# 08_-_TEMP_CONTROL.net
KiCad netlist of a schematic drawn in Altium Designer
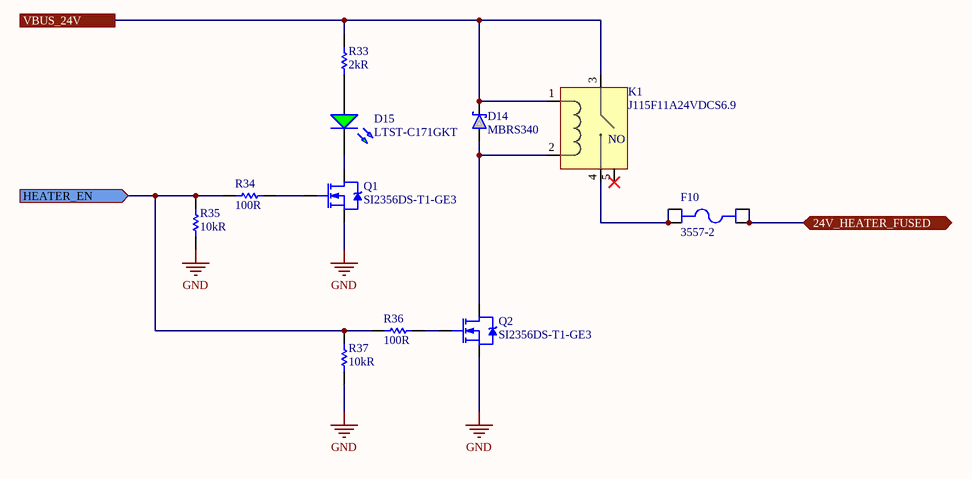
[diagram p0: [08] - TEMP CONTROL.SchDoc]

(export (version "E")
  (design (tool "Eeschema 10.0.6"))
  (components
    (comp (ref "D14")
      (value "MBRS340")
      (footprint "D0-214AB SMC - L")
      (description "DIODE SCHOTTKY 40V 4A SMC")
      (fields (field (name "MANUFACTURER") "ON Semiconductor / Fairchild"))
      (libsource (lib "Diodes") (part "MBRS340"))
    )
    (comp (ref "D15")
      (value "LTST-C171GKT")
      (footprint "LED - 0805 - GREEN")
      (fields (field (name "MANUFACTURER") "Vishay Lite-On"))
      (libsource (lib "LEDs") (part "LTST-C171GKT"))
    )
    (comp (ref "F10")
      (value "3557-2")
      (footprint "KEYSTONE_3557-2")
      (description "Fuse Holder; Auto; 2 in1 Blade; THM; 1 Fuse; Vertical; 30 Amps")
      (fields (field (name "MANUFACTURER") "Keystone Electronics") (field (name "VOLTAGE") "500V"))
      (libsource (lib "Fuses") (part "3557-2"))
    )
    (comp (ref "K1")
      (value "J115F11A24VDCS6.9")
      (footprint "CIT_J115F11A24VDCS6_9")
      (fields (field (name "MANUFACTURER") "CIT Relay & Switch"))
      (libsource (lib "Relays") (part "J115F11A24VDCS6.9"))
    )
    (comp (ref "Q1")
      (value "SI2356DS-T1-GE3")
      (footprint "SOT23-3P95_237X112L50X42N")
      (description "Si2356DS Series 40 V 3.2 A 51 mOhm Surface Mount N-Channel Mosfet - SOT-23-3")
      (fields (field (name "MANUFACTURER") "Vishay Siliconix"))
      (libsource (lib "Transistors - FET") (part "SI2356DS-T1-GE3"))
    )
    (comp (ref "Q2")
      (value "SI2356DS-T1-GE3")
      (footprint "SOT23-3P95_237X112L50X42N")
      (description "Si2356DS Series 40 V 3.2 A 51 mOhm Surface Mount N-Channel Mosfet - SOT-23-3")
      (fields (field (name "MANUFACTURER") "Vishay Siliconix"))
      (libsource (lib "Transistors - FET") (part "SI2356DS-T1-GE3"))
    )
    (comp (ref "R33")
      (value "2kR")
      (footprint "INCH 0805 - METRIC 2012 - H065")
      (description "Res Thick Film 0805 2K Ohm 1% 1/8W ±100ppm/°C Molded SMD Paper T/R")
      (fields
        (field (name "MANUFACTURER") "Vishay")
        (field (name "MANUFACTURER PART NUMBER") "CRCW08052K00FKEA")
      )
      (libsource (lib "Resistors") (part "CRCW08052K00FKEA"))
    )
    (comp (ref "R34")
      (value "100R")
      (footprint "INCH 0603 - METRIC 1608 - H055")
      (description "RES SMD 100 OHM 0.1% 1/16W 0603")
      (fields
        (field (name "MANUFACTURER") "TE Connectivity Neohm")
        (field (name "MANUFACTURER PART NUMBER") "CPF0603B100RE1")
      )
      (libsource (lib "Resistors") (part "CPF0603B100RE1"))
    )
    (comp (ref "R35")
      (value "10kR")
      (footprint "INCH 0603 - METRIC 1508 - H050")
      (description "RES SMD 10K OHM 5% 1/10W 0603")
      (fields
        (field (name "MANUFACTURER") "Vishay Dale")
        (field (name "MANUFACTURER PART NUMBER") "CRCW060310K0JNEA")
      )
      (libsource (lib "Resistors") (part "CRCW060310K0JNEA"))
    )
    (comp (ref "R36")
      (value "100R")
      (footprint "INCH 0603 - METRIC 1608 - H055")
      (description "RES SMD 100 OHM 0.1% 1/16W 0603")
      (fields
        (field (name "MANUFACTURER") "TE Connectivity Neohm")
        (field (name "MANUFACTURER PART NUMBER") "CPF0603B100RE1")
      )
      (libsource (lib "Resistors") (part "CPF0603B100RE1"))
    )
    (comp (ref "R37")
      (value "10kR")
      (footprint "INCH 0603 - METRIC 1508 - H050")
      (description "RES SMD 10K OHM 5% 1/10W 0603")
      (fields
        (field (name "MANUFACTURER") "Vishay Dale")
        (field (name "MANUFACTURER PART NUMBER") "CRCW060310K0JNEA")
      )
      (libsource (lib "Resistors") (part "CRCW060310K0JNEA"))
    )
  )
  (nets
    (net (code "1") (name "/24V_HEATER_FUSED") (class "Default")
      (node (ref "F10") (pin "3") (pinfunction "3_3") (pintype "passive"))
      (node (ref "F10") (pin "4") (pinfunction "4_4") (pintype "passive"))
    )
    (net (code "2") (name "/HEATER_EN") (class "Default")
      (node (ref "R34") (pin "1") (pintype "passive"))
      (node (ref "R35") (pin "1") (pintype "passive"))
      (node (ref "R36") (pin "1") (pintype "passive"))
      (node (ref "R37") (pin "1") (pintype "passive"))
    )
    (net (code "3") (name "/VBUS_24V") (class "Default")
      (node (ref "D14") (pin "1") (pintype "passive"))
      (node (ref "K1") (pin "1") (pinfunction "1_1") (pintype "passive"))
      (node (ref "K1") (pin "3") (pinfunction "3_3") (pintype "passive"))
      (node (ref "R33") (pin "1") (pintype "passive"))
    )
    (net (code "4") (name "GND") (class "Default")
      (node (ref "Q1") (pin "2") (pinfunction "S_2") (pintype "passive"))
      (node (ref "Q2") (pin "2") (pinfunction "S_2") (pintype "passive"))
      (node (ref "R35") (pin "2") (pintype "passive"))
      (node (ref "R37") (pin "2") (pintype "passive"))
    )
    (net (code "5") (name "Net-(D15-PadA)") (class "Default")
      (node (ref "D15") (pin "A") (pintype "passive"))
      (node (ref "R33") (pin "2") (pintype "passive"))
    )
    (net (code "6") (name "Net-(F10-Pad1)") (class "Default")
      (node (ref "F10") (pin "1") (pinfunction "1_1") (pintype "passive"))
      (node (ref "F10") (pin "2") (pinfunction "2_2") (pintype "passive"))
      (node (ref "K1") (pin "4") (pinfunction "4_4") (pintype "passive"))
    )
    (net (code "7") (name "Net-(Q1-D)") (class "Default")
      (node (ref "D15") (pin "C") (pintype "passive"))
      (node (ref "Q1") (pin "3") (pinfunction "D_3") (pintype "passive"))
    )
    (net (code "8") (name "Net-(Q1-G)") (class "Default")
      (node (ref "Q1") (pin "1") (pinfunction "G_1") (pintype "passive"))
      (node (ref "R34") (pin "2") (pintype "passive"))
    )
    (net (code "9") (name "Net-(Q2-D)") (class "Default")
      (node (ref "D14") (pin "2") (pintype "passive"))
      (node (ref "K1") (pin "2") (pinfunction "2_2") (pintype "passive"))
      (node (ref "Q2") (pin "3") (pinfunction "D_3") (pintype "passive"))
    )
    (net (code "10") (name "Net-(Q2-G)") (class "Default")
      (node (ref "Q2") (pin "1") (pinfunction "G_1") (pintype "passive"))
      (node (ref "R36") (pin "2") (pintype "passive"))
    )
    (net (code "11") (name "unconnected-(K1-Pad5)") (class "Default")
      (node (ref "K1") (pin "5") (pinfunction "5_5") (pintype "passive+no_connect"))
    )
  )
)
